# Sequencer-V02-023e.net
KiCad netlist of a schematic drawn in EAGLE
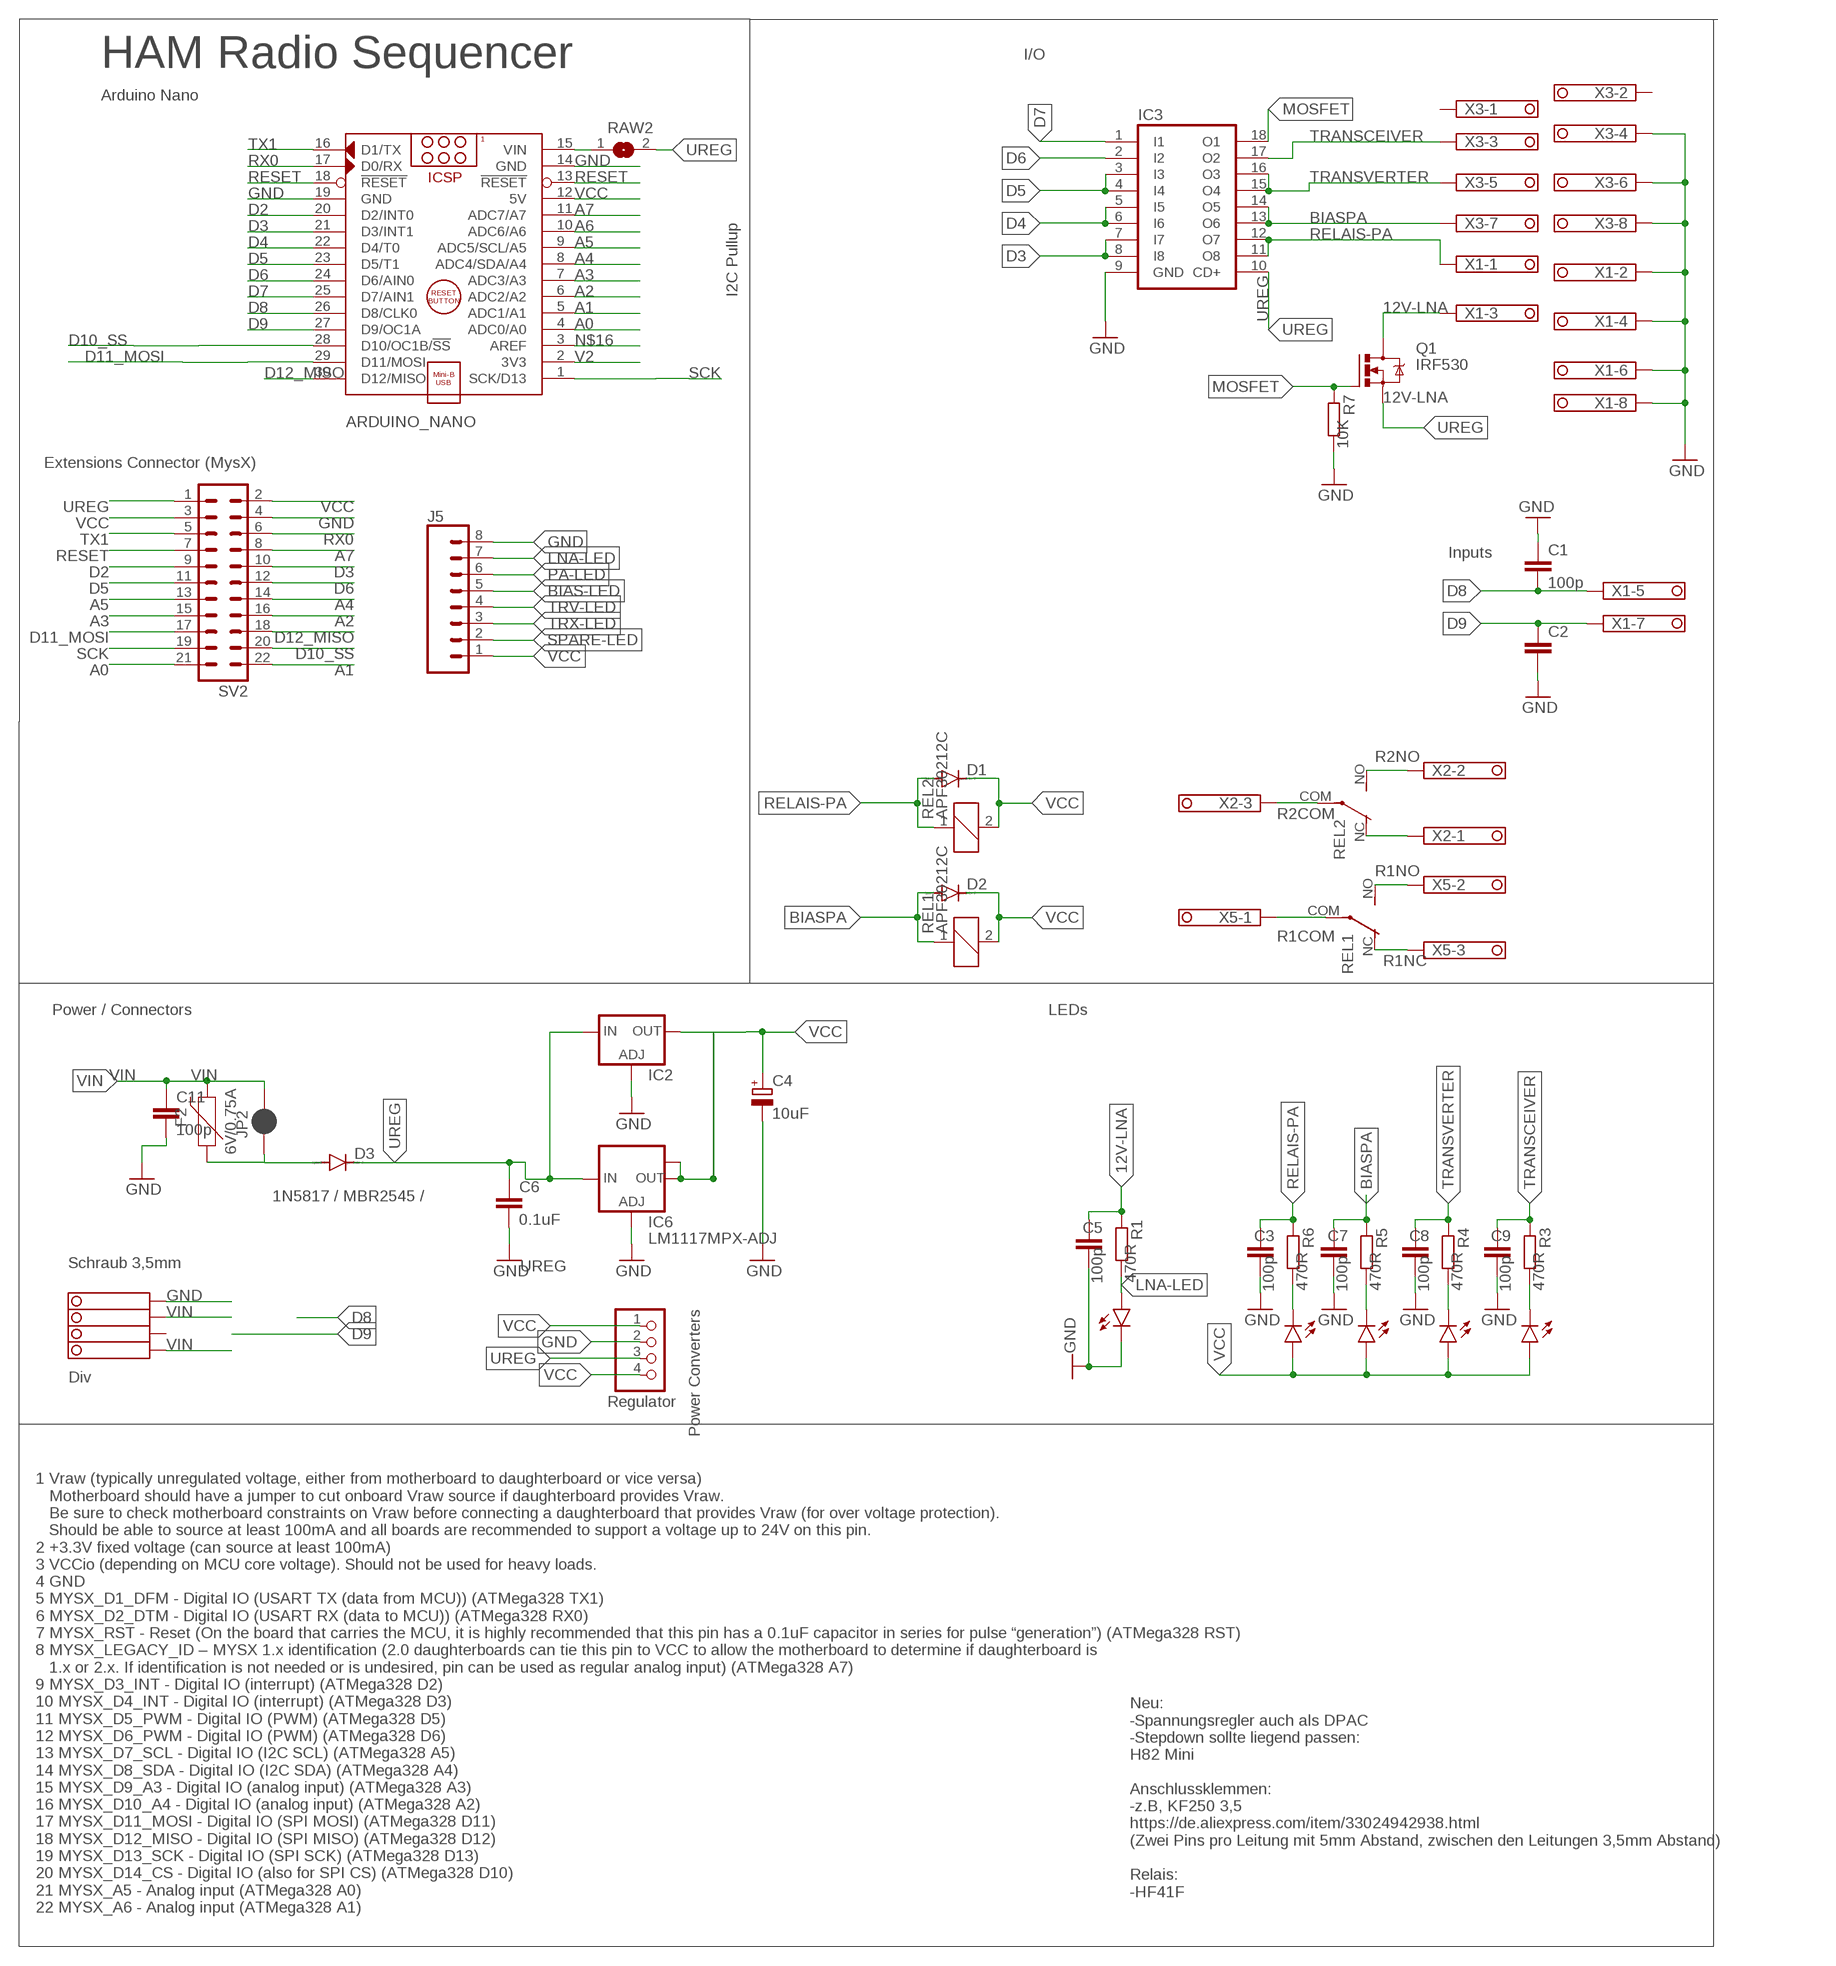
[diagram p0: schematic, sheet 1]

(export (version "E")
  (design (tool "Eeschema 10.0.6"))
  (components
    (comp (ref "ARDUINO_NANO")
      (value "ARDUINO_NANO_OHNE-BOHR")
      (footprint "eagle-import:ARDUINO_NANO")
      (libsource (lib "eagle-import") (part "ARDUINO_NANO_OHNE-BOHR"))
    )
    (comp (ref "C1")
      (value "100p")
      (footprint "eagle-import:C025-025X050")
      (libsource (lib "eagle-import") (part "C-EU025-025X050"))
    )
    (comp (ref "C2")
      (value "C-EU025-025X050")
      (footprint "eagle-import:C025-025X050")
      (libsource (lib "eagle-import") (part "C-EU025-025X050"))
    )
    (comp (ref "C3")
      (value "100p")
      (footprint "eagle-import:C025-025X050")
      (libsource (lib "eagle-import") (part "C-EU025-025X050"))
    )
    (comp (ref "C4")
      (value "10uF")
      (footprint "eagle-import:E3,5-8")
      (libsource (lib "eagle-import") (part "CPOL-EUE3.5-8"))
    )
    (comp (ref "C5")
      (value "100p")
      (footprint "eagle-import:C025-025X050")
      (libsource (lib "eagle-import") (part "C-EU025-025X050"))
    )
    (comp (ref "C6")
      (value "0.1uF")
      (footprint "eagle-import:C050-024X044")
      (libsource (lib "eagle-import") (part "C-EU050-024X044"))
    )
    (comp (ref "C7")
      (value "100p")
      (footprint "eagle-import:C025-025X050")
      (libsource (lib "eagle-import") (part "C-EU025-025X050"))
    )
    (comp (ref "C8")
      (value "100p")
      (footprint "eagle-import:C025-025X050")
      (libsource (lib "eagle-import") (part "C-EU025-025X050"))
    )
    (comp (ref "C9")
      (value "100p")
      (footprint "eagle-import:C025-025X050")
      (libsource (lib "eagle-import") (part "C-EU025-025X050"))
    )
    (comp (ref "C11")
      (value "100p")
      (footprint "eagle-import:C025-025X050")
      (libsource (lib "eagle-import") (part "C-EU025-025X050"))
    )
    (comp (ref "D1")
      (value "DIODE-D-2.5")
      (footprint "eagle-import:D-2.5")
      (libsource (lib "eagle-import") (part "DIODE-D-2.5"))
    )
    (comp (ref "D2")
      (value "DIODE-D-2.5")
      (footprint "eagle-import:D-2.5")
      (libsource (lib "eagle-import") (part "DIODE-D-2.5"))
    )
    (comp (ref "D3")
      (value "1N5817 / MBR2545 /")
      (footprint "eagle-import:D-7.5")
      (libsource (lib "eagle-import") (part "DIODE-D-7.5"))
    )
    (comp (ref "F2")
      (value "6V/0.75A")
      (footprint "eagle-import:1206")
      (libsource (lib "eagle-import") (part "PPTC_THREE-QUARTER-AMP"))
    )
    (comp (ref "IC2")
      (value "LD117ADT50TR")
      (footprint "eagle-import:DPACK")
      (libsource (lib "eagle-import") (part "LD117A?DT50TR"))
    )
    (comp (ref "IC3")
      (value "ULN2803A")
      (footprint "eagle-import:DIL18")
      (libsource (lib "eagle-import") (part "ULN2803A"))
    )
    (comp (ref "IC6")
      (value "LM1117MPX-ADJ")
      (footprint "eagle-import:SOT223")
      (libsource (lib "eagle-import") (part "LM1117MPX-ADJ"))
    )
    (comp (ref "J5")
      (value "CONN_08LOCK")
      (footprint "eagle-import:1X08_LOCK")
      (libsource (lib "eagle-import") (part "CONN_08LOCK"))
    )
    (comp (ref "JP2")
      (value "JUMPER-SMT_2_NC_PASTE_NO-SILK")
      (footprint "eagle-import:SMT-JUMPER_2_NC_PASTE_NO-SILK")
      (libsource (lib "eagle-import") (part "JUMPER-SMT_2_NC_PASTE_NO-SILK"))
    )
    (comp (ref "LED-BIAS")
      (value "LED3MM")
      (footprint "eagle-import:LED3MM")
      (libsource (lib "eagle-import") (part "LED3MM"))
    )
    (comp (ref "LED-LNA")
      (value "LED3MM")
      (footprint "eagle-import:LED3MM")
      (libsource (lib "eagle-import") (part "LED3MM"))
    )
    (comp (ref "LED-PA")
      (value "LED3MM")
      (footprint "eagle-import:LED3MM")
      (libsource (lib "eagle-import") (part "LED3MM"))
    )
    (comp (ref "LED-TRV")
      (value "LED3MM")
      (footprint "eagle-import:LED3MM")
      (libsource (lib "eagle-import") (part "LED3MM"))
    )
    (comp (ref "LED-TRX")
      (value "LED3MM")
      (footprint "eagle-import:LED3MM")
      (libsource (lib "eagle-import") (part "LED3MM"))
    )
    (comp (ref "Q1")
      (value "IRF530")
      (footprint "eagle-import:TO220BV")
      (libsource (lib "eagle-import") (part "IRF530"))
    )
    (comp (ref "R1")
      (value "470R")
      (footprint "eagle-import:0207_7")
      (libsource (lib "eagle-import") (part "R-EU_0207/7"))
    )
    (comp (ref "R3")
      (value "470R")
      (footprint "eagle-import:0207_7")
      (libsource (lib "eagle-import") (part "R-EU_0207/7"))
    )
    (comp (ref "R4")
      (value "470R")
      (footprint "eagle-import:0207_7")
      (libsource (lib "eagle-import") (part "R-EU_0207/7"))
    )
    (comp (ref "R5")
      (value "470R")
      (footprint "eagle-import:0207_7")
      (libsource (lib "eagle-import") (part "R-EU_0207/7"))
    )
    (comp (ref "R6")
      (value "470R")
      (footprint "eagle-import:0207_7")
      (libsource (lib "eagle-import") (part "R-EU_0207/7"))
    )
    (comp (ref "R7")
      (value "10K")
      (footprint "eagle-import:0207_7")
      (libsource (lib "eagle-import") (part "R-EU_0207/7"))
    )
    (comp (ref "RAW2")
      (value "SJ")
      (footprint "eagle-import:SJ")
      (libsource (lib "eagle-import") (part "SJ"))
    )
    (comp (ref "REL1")
      (value "APF30212C")
      (footprint "eagle-import:APF30212C")
      (libsource (lib "eagle-import") (part "APF30212C"))
    )
    (comp (ref "REL2")
      (value "APF30212C")
      (footprint "eagle-import:APF30212C")
      (libsource (lib "eagle-import") (part "APF30212C"))
    )
    (comp (ref "STEPDWN")
      (value "PINHD-1X04_2.54-S")
      (footprint "eagle-import:1X04-S")
      (libsource (lib "eagle-import") (part "PINHD-1X04_2.54-S"))
    )
    (comp (ref "SV2")
      (value "MA11-2")
      (footprint "eagle-import:MA11-2")
      (libsource (lib "eagle-import") (part "MA11-2"))
    )
    (comp (ref "X1")
      (value "MARTIN8X2-1751303")
      (footprint "eagle-import:1751303")
      (libsource (lib "eagle-import") (part "MARTIN8X2-1751303"))
    )
    (comp (ref "X2")
      (value "MARTIN3X2-1751303175L303-3")
      (footprint "eagle-import:1751303-3")
      (libsource (lib "eagle-import") (part "MARTIN3X2-1751303175L303-3"))
    )
    (comp (ref "X3")
      (value "MARTIN8X2-1751303")
      (footprint "eagle-import:1751303")
      (libsource (lib "eagle-import") (part "MARTIN8X2-1751303"))
    )
    (comp (ref "X4")
      (value "1751264")
      (footprint "eagle-import:1751264")
      (libsource (lib "eagle-import") (part "1751264"))
    )
    (comp (ref "X5")
      (value "MARTIN3X2-1751303175L303-3")
      (footprint "eagle-import:1751303-3")
      (libsource (lib "eagle-import") (part "MARTIN3X2-1751303175L303-3"))
    )
  )
  (nets
    (net (code "1") (name "/A0") (class "Default")
      (node (ref "ARDUINO_NANO") (pin "4") (pinfunction "ADC0/A0_4") (pintype "bidirectional"))
      (node (ref "SV2") (pin "21") (pinfunction "21_21") (pintype "passive"))
    )
    (net (code "2") (name "/A1") (class "Default")
      (node (ref "ARDUINO_NANO") (pin "5") (pinfunction "ADC1/A1_5") (pintype "bidirectional"))
      (node (ref "SV2") (pin "22") (pinfunction "22_22") (pintype "passive"))
    )
    (net (code "3") (name "/A2") (class "Default")
      (node (ref "ARDUINO_NANO") (pin "6") (pinfunction "ADC2/A2_6") (pintype "bidirectional"))
      (node (ref "SV2") (pin "16") (pinfunction "16_16") (pintype "passive"))
    )
    (net (code "4") (name "/A3") (class "Default")
      (node (ref "ARDUINO_NANO") (pin "7") (pinfunction "ADC3/A3_7") (pintype "bidirectional"))
      (node (ref "SV2") (pin "15") (pinfunction "15_15") (pintype "passive"))
    )
    (net (code "5") (name "/A4") (class "Default")
      (node (ref "ARDUINO_NANO") (pin "8") (pinfunction "ADC4/SDA/A4_8") (pintype "bidirectional"))
      (node (ref "SV2") (pin "14") (pinfunction "14_14") (pintype "passive"))
    )
    (net (code "6") (name "/A5") (class "Default")
      (node (ref "ARDUINO_NANO") (pin "9") (pinfunction "ADC5/SCL/A5_9") (pintype "bidirectional"))
      (node (ref "SV2") (pin "13") (pinfunction "13_13") (pintype "passive"))
    )
    (net (code "7") (name "/A6") (class "Default")
      (node (ref "ARDUINO_NANO") (pin "10") (pinfunction "ADC6/A6_10") (pintype "bidirectional"))
    )
    (net (code "8") (name "/A7") (class "Default")
      (node (ref "ARDUINO_NANO") (pin "11") (pinfunction "ADC7/A7_11") (pintype "bidirectional"))
      (node (ref "SV2") (pin "8") (pinfunction "8_8") (pintype "passive"))
    )
    (net (code "9") (name "/D2") (class "Default")
      (node (ref "ARDUINO_NANO") (pin "20") (pinfunction "D2/INT0_20") (pintype "bidirectional"))
      (node (ref "SV2") (pin "9") (pinfunction "9_9") (pintype "passive"))
    )
    (net (code "10") (name "/D10_SS") (class "Default")
      (node (ref "ARDUINO_NANO") (pin "28") (pinfunction "D10/OC1B/~{SS}_28") (pintype "bidirectional"))
      (node (ref "SV2") (pin "20") (pinfunction "20_20") (pintype "passive"))
    )
    (net (code "11") (name "/D11_MOSI") (class "Default")
      (node (ref "ARDUINO_NANO") (pin "29") (pinfunction "D11/MOSI_29") (pintype "bidirectional"))
      (node (ref "SV2") (pin "17") (pinfunction "17_17") (pintype "passive"))
    )
    (net (code "12") (name "/D12_MISO") (class "Default")
      (node (ref "ARDUINO_NANO") (pin "30") (pinfunction "D12/MISO_30") (pintype "bidirectional"))
      (node (ref "SV2") (pin "18") (pinfunction "18_18") (pintype "passive"))
    )
    (net (code "13") (name "/N$16") (class "Default")
      (node (ref "ARDUINO_NANO") (pin "3") (pinfunction "AREF_3") (pintype "input"))
    )
    (net (code "14") (name "/R1COM") (class "Default")
      (node (ref "REL1") (pin "COM") (pinfunction "P_COM") (pintype "passive"))
      (node (ref "X5") (pin "1") (pinfunction "K_1") (pintype "passive"))
    )
    (net (code "15") (name "/R1NC") (class "Default")
      (node (ref "REL1") (pin "NC") (pinfunction "O_NC") (pintype "passive"))
      (node (ref "X5") (pin "3") (pinfunction "K_3") (pintype "passive"))
    )
    (net (code "16") (name "/R1NO") (class "Default")
      (node (ref "REL1") (pin "NO") (pinfunction "S_NO") (pintype "passive"))
      (node (ref "X5") (pin "2") (pinfunction "K_2") (pintype "passive"))
    )
    (net (code "17") (name "/R2COM") (class "Default")
      (node (ref "REL2") (pin "COM") (pinfunction "P_COM") (pintype "passive"))
      (node (ref "X2") (pin "3") (pinfunction "K_3") (pintype "passive"))
    )
    (net (code "18") (name "/R2NO") (class "Default")
      (node (ref "REL2") (pin "NO") (pinfunction "S_NO") (pintype "passive"))
      (node (ref "X2") (pin "2") (pinfunction "K_2") (pintype "passive"))
    )
    (net (code "19") (name "/RESET") (class "Default")
      (node (ref "ARDUINO_NANO") (pin "13") (pinfunction "~{RESET}_13") (pintype "input"))
      (node (ref "ARDUINO_NANO") (pin "18") (pinfunction "~{RESET}_18") (pintype "input"))
      (node (ref "SV2") (pin "7") (pinfunction "7_7") (pintype "passive"))
    )
    (net (code "20") (name "/RX0") (class "Default")
      (node (ref "ARDUINO_NANO") (pin "17") (pinfunction "D0/RX_17") (pintype "bidirectional"))
      (node (ref "SV2") (pin "6") (pinfunction "6_6") (pintype "passive"))
    )
    (net (code "21") (name "/SCK") (class "Default")
      (node (ref "ARDUINO_NANO") (pin "1") (pinfunction "SCK/D13_1") (pintype "bidirectional"))
      (node (ref "SV2") (pin "19") (pinfunction "19_19") (pintype "passive"))
    )
    (net (code "22") (name "/TX1") (class "Default")
      (node (ref "ARDUINO_NANO") (pin "16") (pinfunction "D1/TX_16") (pintype "bidirectional"))
      (node (ref "SV2") (pin "5") (pinfunction "5_5") (pintype "passive"))
    )
    (net (code "23") (name "/V2") (class "Default")
      (node (ref "ARDUINO_NANO") (pin "2") (pinfunction "3V3_2") (pintype "output"))
    )
    (net (code "24") (name "12V-LNA") (class "Default")
      (node (ref "C5") (pin "1") (pinfunction "1_1") (pintype "passive"))
      (node (ref "Q1") (pin "D") (pinfunction "D_D") (pintype "passive"))
      (node (ref "R1") (pin "1") (pinfunction "1_1") (pintype "passive"))
      (node (ref "X1") (pin "11") (pinfunction "K_11") (pintype "passive"))
    )
    (net (code "25") (name "BIAS-LED") (class "Default")
      (node (ref "J5") (pin "5") (pinfunction "5_5") (pintype "passive"))
      (node (ref "LED-BIAS") (pin "K") (pinfunction "C_K") (pintype "passive"))
      (node (ref "R5") (pin "2") (pinfunction "2_2") (pintype "passive"))
    )
    (net (code "26") (name "BIASPA") (class "Default")
      (node (ref "C7") (pin "1") (pinfunction "1_1") (pintype "passive"))
      (node (ref "D2") (pin "A") (pinfunction "A_A") (pintype "passive"))
      (node (ref "IC3") (pin "13") (pinfunction "O6_13") (pintype "open_collector"))
      (node (ref "IC3") (pin "14") (pinfunction "O5_14") (pintype "open_collector"))
      (node (ref "R5") (pin "1") (pinfunction "1_1") (pintype "passive"))
      (node (ref "REL1") (pin "1") (pinfunction "1_1") (pintype "passive"))
      (node (ref "X3") (pin "15") (pinfunction "K_15") (pintype "passive"))
    )
    (net (code "27") (name "D3") (class "Default")
      (node (ref "ARDUINO_NANO") (pin "21") (pinfunction "D3/INT1_21") (pintype "bidirectional"))
      (node (ref "IC3") (pin "7") (pinfunction "I7_7") (pintype "input"))
      (node (ref "IC3") (pin "8") (pinfunction "I8_8") (pintype "input"))
      (node (ref "SV2") (pin "10") (pinfunction "10_10") (pintype "passive"))
    )
    (net (code "28") (name "D4") (class "Default")
      (node (ref "ARDUINO_NANO") (pin "22") (pinfunction "D4/T0_22") (pintype "bidirectional"))
      (node (ref "IC3") (pin "5") (pinfunction "I5_5") (pintype "input"))
      (node (ref "IC3") (pin "6") (pinfunction "I6_6") (pintype "input"))
    )
    (net (code "29") (name "D5") (class "Default")
      (node (ref "ARDUINO_NANO") (pin "23") (pinfunction "D5/T1_23") (pintype "bidirectional"))
      (node (ref "IC3") (pin "3") (pinfunction "I3_3") (pintype "input"))
      (node (ref "IC3") (pin "4") (pinfunction "I4_4") (pintype "input"))
      (node (ref "SV2") (pin "11") (pinfunction "11_11") (pintype "passive"))
    )
    (net (code "30") (name "D6") (class "Default")
      (node (ref "ARDUINO_NANO") (pin "24") (pinfunction "D6/AIN0_24") (pintype "bidirectional"))
      (node (ref "IC3") (pin "2") (pinfunction "I2_2") (pintype "input"))
      (node (ref "SV2") (pin "12") (pinfunction "12_12") (pintype "passive"))
    )
    (net (code "31") (name "D7") (class "Default")
      (node (ref "ARDUINO_NANO") (pin "25") (pinfunction "D7/AIN1_25") (pintype "bidirectional"))
      (node (ref "IC3") (pin "1") (pinfunction "I1_1") (pintype "input"))
    )
    (net (code "32") (name "D8") (class "Default")
      (node (ref "ARDUINO_NANO") (pin "26") (pinfunction "D8/CLK0_26") (pintype "bidirectional"))
      (node (ref "C1") (pin "2") (pinfunction "2_2") (pintype "passive"))
      (node (ref "X1") (pin "13") (pinfunction "K_13") (pintype "passive"))
    )
    (net (code "33") (name "D9") (class "Default")
      (node (ref "ARDUINO_NANO") (pin "27") (pinfunction "D9/OC1A_27") (pintype "bidirectional"))
      (node (ref "C2") (pin "1") (pinfunction "1_1") (pintype "passive"))
      (node (ref "X1") (pin "15") (pinfunction "K_15") (pintype "passive"))
    )
    (net (code "34") (name "GND") (class "Default")
      (node (ref "ARDUINO_NANO") (pin "14") (pinfunction "GND_14") (pintype "power_in"))
      (node (ref "ARDUINO_NANO") (pin "19") (pinfunction "GND_19") (pintype "power_in"))
      (node (ref "C1") (pin "1") (pinfunction "1_1") (pintype "passive"))
      (node (ref "C11") (pin "2") (pinfunction "2_2") (pintype "passive"))
      (node (ref "C2") (pin "2") (pinfunction "2_2") (pintype "passive"))
      (node (ref "C3") (pin "2") (pinfunction "2_2") (pintype "passive"))
      (node (ref "C4") (pin "-") (pinfunction "-_-") (pintype "passive"))
      (node (ref "C5") (pin "2") (pinfunction "2_2") (pintype "passive"))
      (node (ref "C6") (pin "2") (pinfunction "2_2") (pintype "passive"))
      (node (ref "C7") (pin "2") (pinfunction "2_2") (pintype "passive"))
      (node (ref "C8") (pin "2") (pinfunction "2_2") (pintype "passive"))
      (node (ref "C9") (pin "2") (pinfunction "2_2") (pintype "passive"))
      (node (ref "IC2") (pin "1") (pinfunction "ADJ_1") (pintype "input"))
      (node (ref "IC3") (pin "9") (pinfunction "GND_9") (pintype "power_in"))
      (node (ref "IC6") (pin "1") (pinfunction "ADJ_1") (pintype "input"))
      (node (ref "J5") (pin "8") (pinfunction "8_8") (pintype "passive"))
      (node (ref "LED-LNA") (pin "K") (pinfunction "C_K") (pintype "passive"))
      (node (ref "R7") (pin "2") (pinfunction "2_2") (pintype "passive"))
      (node (ref "STEPDWN") (pin "2") (pinfunction "2_2") (pintype "passive"))
      (node (ref "SV2") (pin "4") (pinfunction "4_4") (pintype "passive"))
      (node (ref "X1") (pin "10") (pinfunction "K_10") (pintype "passive"))
      (node (ref "X1") (pin "12") (pinfunction "K_12") (pintype "passive"))
      (node (ref "X1") (pin "14") (pinfunction "K_14") (pintype "passive"))
      (node (ref "X1") (pin "16") (pinfunction "K_16") (pintype "passive"))
      (node (ref "X3") (pin "12") (pinfunction "K_12") (pintype "passive"))
      (node (ref "X3") (pin "14") (pinfunction "K_14") (pintype "passive"))
      (node (ref "X3") (pin "16") (pinfunction "K_16") (pintype "passive"))
      (node (ref "X4") (pin "4") (pinfunction "K_4") (pintype "passive"))
    )
    (net (code "35") (name "LNA-LED") (class "Default")
      (node (ref "J5") (pin "7") (pinfunction "7_7") (pintype "passive"))
      (node (ref "LED-LNA") (pin "A") (pinfunction "A_A") (pintype "passive"))
      (node (ref "R1") (pin "2") (pinfunction "2_2") (pintype "passive"))
    )
    (net (code "36") (name "MOSFET") (class "Default")
      (node (ref "IC3") (pin "18") (pinfunction "O1_18") (pintype "open_collector"))
      (node (ref "Q1") (pin "G") (pinfunction "G_G") (pintype "passive"))
      (node (ref "R7") (pin "1") (pinfunction "1_1") (pintype "passive"))
    )
    (net (code "37") (name "Net-(ARDUINO_NANO-VIN)") (class "Default")
      (node (ref "ARDUINO_NANO") (pin "15") (pinfunction "VIN_15") (pintype "power_in"))
      (node (ref "RAW2") (pin "1") (pinfunction "1_1") (pintype "passive"))
    )
    (net (code "38") (name "Net-(D3-PadA)") (class "Default")
      (node (ref "D3") (pin "A") (pinfunction "A_A") (pintype "passive"))
      (node (ref "F2") (pin "1") (pinfunction "1_1") (pintype "bidirectional"))
      (node (ref "JP2") (pin "1") (pinfunction "1_1") (pintype "passive"))
    )
    (net (code "39") (name "Net-(REL2B-O)") (class "Default")
      (node (ref "REL2") (pin "NC") (pinfunction "O_NC") (pintype "passive"))
      (node (ref "X2") (pin "1") (pinfunction "K_1") (pintype "passive"))
    )
    (net (code "40") (name "PA-LED") (class "Default")
      (node (ref "J5") (pin "6") (pinfunction "6_6") (pintype "passive"))
      (node (ref "LED-PA") (pin "K") (pinfunction "C_K") (pintype "passive"))
      (node (ref "R6") (pin "2") (pinfunction "2_2") (pintype "passive"))
    )
    (net (code "41") (name "RELAIS-PA") (class "Default")
      (node (ref "C3") (pin "1") (pinfunction "1_1") (pintype "passive"))
      (node (ref "D1") (pin "A") (pinfunction "A_A") (pintype "passive"))
      (node (ref "IC3") (pin "11") (pinfunction "O8_11") (pintype "open_collector"))
      (node (ref "IC3") (pin "12") (pinfunction "O7_12") (pintype "open_collector"))
      (node (ref "R6") (pin "1") (pinfunction "1_1") (pintype "passive"))
      (node (ref "REL2") (pin "1") (pinfunction "1_1") (pintype "passive"))
      (node (ref "X1") (pin "9") (pinfunction "K_9") (pintype "passive"))
    )
    (net (code "42") (name "SPARE-LED") (class "Default")
      (node (ref "J5") (pin "2") (pinfunction "2_2") (pintype "passive"))
    )
    (net (code "43") (name "TRANSCEIVER") (class "Default")
      (node (ref "C9") (pin "1") (pinfunction "1_1") (pintype "passive"))
      (node (ref "IC3") (pin "17") (pinfunction "O2_17") (pintype "open_collector"))
      (node (ref "R3") (pin "1") (pinfunction "1_1") (pintype "passive"))
      (node (ref "X3") (pin "11") (pinfunction "K_11") (pintype "passive"))
    )
    (net (code "44") (name "TRANSVERTER") (class "Default")
      (node (ref "C8") (pin "1") (pinfunction "1_1") (pintype "passive"))
      (node (ref "IC3") (pin "15") (pinfunction "O4_15") (pintype "open_collector"))
      (node (ref "IC3") (pin "16") (pinfunction "O3_16") (pintype "open_collector"))
      (node (ref "R4") (pin "1") (pinfunction "1_1") (pintype "passive"))
      (node (ref "X3") (pin "13") (pinfunction "K_13") (pintype "passive"))
    )
    (net (code "45") (name "TRV-LED") (class "Default")
      (node (ref "J5") (pin "4") (pinfunction "4_4") (pintype "passive"))
      (node (ref "LED-TRV") (pin "K") (pinfunction "C_K") (pintype "passive"))
      (node (ref "R4") (pin "2") (pinfunction "2_2") (pintype "passive"))
    )
    (net (code "46") (name "TRX-LED") (class "Default")
      (node (ref "J5") (pin "3") (pinfunction "3_3") (pintype "passive"))
      (node (ref "LED-TRX") (pin "K") (pinfunction "C_K") (pintype "passive"))
      (node (ref "R3") (pin "2") (pinfunction "2_2") (pintype "passive"))
    )
    (net (code "47") (name "UREG") (class "Default")
      (node (ref "C6") (pin "1") (pinfunction "1_1") (pintype "passive"))
      (node (ref "D3") (pin "C") (pinfunction "C_C") (pintype "passive"))
      (node (ref "IC2") (pin "3") (pinfunction "IN_3") (pintype "input"))
      (node (ref "IC3") (pin "10") (pinfunction "CD+_10") (pintype "passive"))
      (node (ref "IC6") (pin "3") (pinfunction "IN_3") (pintype "input"))
      (node (ref "Q1") (pin "S") (pinfunction "S_S") (pintype "passive"))
      (node (ref "RAW2") (pin "2") (pinfunction "2_2") (pintype "passive"))
      (node (ref "STEPDWN") (pin "3") (pinfunction "3_3") (pintype "passive"))
      (node (ref "SV2") (pin "1") (pinfunction "1_1") (pintype "passive"))
    )
    (net (code "48") (name "VCC") (class "Default")
      (node (ref "ARDUINO_NANO") (pin "12") (pinfunction "5V_12") (pintype "power_in"))
      (node (ref "C4") (pin "+") (pinfunction "+_+") (pintype "passive"))
      (node (ref "D1") (pin "C") (pinfunction "C_C") (pintype "passive"))
      (node (ref "D2") (pin "C") (pinfunction "C_C") (pintype "passive"))
      (node (ref "IC2") (pin "4") (pinfunction "OUT_4") (pintype "passive"))
      (node (ref "IC6") (pin "2") (pinfunction "OUT_2") (pintype "passive"))
      (node (ref "IC6") (pin "TAB") (pinfunction "OUT1_TAB") (pintype "passive"))
      (node (ref "J5") (pin "1") (pinfunction "1_1") (pintype "passive"))
      (node (ref "LED-BIAS") (pin "A") (pinfunction "A_A") (pintype "passive"))
      (node (ref "LED-PA") (pin "A") (pinfunction "A_A") (pintype "passive"))
      (node (ref "LED-TRV") (pin "A") (pinfunction "A_A") (pintype "passive"))
      (node (ref "LED-TRX") (pin "A") (pinfunction "A_A") (pintype "passive"))
      (node (ref "REL1") (pin "2") (pinfunction "2_2") (pintype "passive"))
      (node (ref "REL2") (pin "2") (pinfunction "2_2") (pintype "passive"))
      (node (ref "STEPDWN") (pin "1") (pinfunction "1_1") (pintype "passive"))
      (node (ref "STEPDWN") (pin "4") (pinfunction "4_4") (pintype "passive"))
      (node (ref "SV2") (pin "2") (pinfunction "2_2") (pintype "passive"))
      (node (ref "SV2") (pin "3") (pinfunction "3_3") (pintype "passive"))
    )
    (net (code "49") (name "VIN") (class "Default")
      (node (ref "C11") (pin "1") (pinfunction "1_1") (pintype "passive"))
      (node (ref "F2") (pin "2") (pinfunction "2_2") (pintype "bidirectional"))
      (node (ref "JP2") (pin "2") (pinfunction "2_2") (pintype "passive"))
      (node (ref "X4") (pin "1") (pinfunction "K_1") (pintype "passive"))
      (node (ref "X4") (pin "3") (pinfunction "K_3") (pintype "passive"))
    )
    (net (code "50") (name "unconnected-(X3A-K-Pad9)") (class "Default")
      (node (ref "X3") (pin "9") (pinfunction "K_9") (pintype "passive"))
    )
    (net (code "51") (name "unconnected-(X3B-K-Pad10)") (class "Default")
      (node (ref "X3") (pin "10") (pinfunction "K_10") (pintype "passive"))
    )
    (net (code "52") (name "unconnected-(X4B-K-Pad2)") (class "Default")
      (node (ref "X4") (pin "2") (pinfunction "K_2") (pintype "passive"))
    )
  )
)
